# 02_-_WIRELESS_CHARGE.net
KiCad netlist of a schematic drawn in Altium Designer
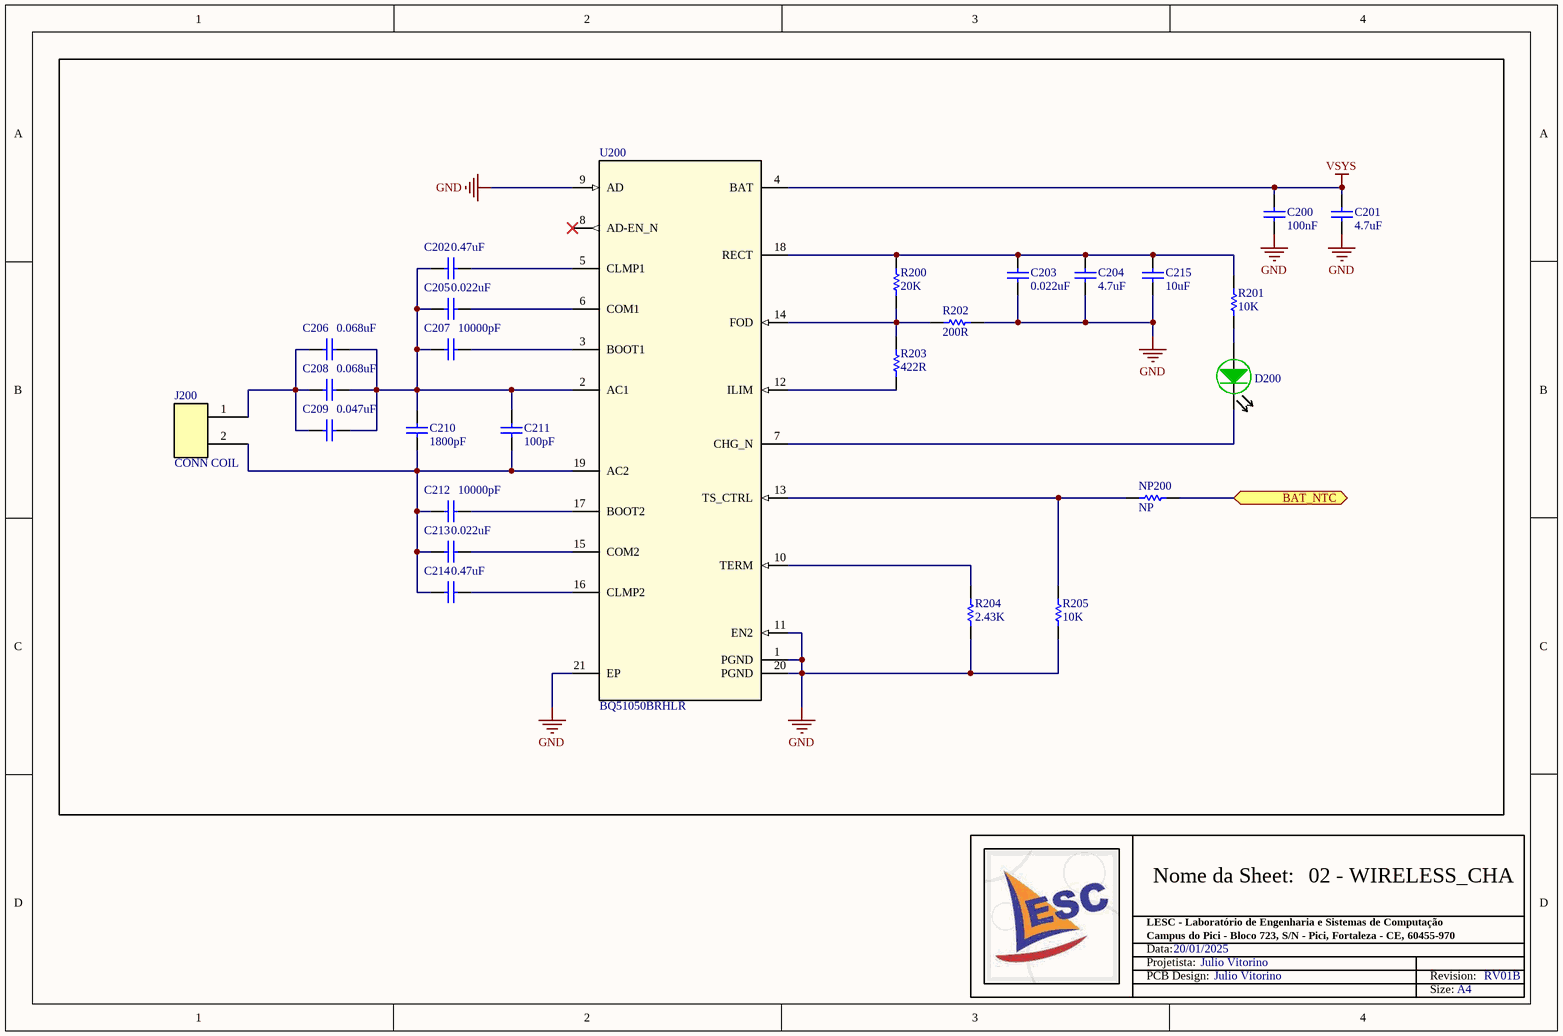
[diagram p0: 02 - WIRELESS_CHARGE.SchDoc]

(export (version "E")
  (design (tool "Eeschema 10.0.6"))
  (components
    (comp (ref "C200")
      (value "100nF")
      (footprint "0402-C-R")
      (description "CAP SMD 0402 MLCC GERAL 100nF 10V ±20% 0402 X7R PN:C0402C104K8RACTU KEMET")
      (fields (field (name "VOLTAGE") "10V") (field (name "TOLERANCE") "20%"))
      (libsource (lib "Schlib1") (part "CAP SMD 0402 100nF 10V ±20%"))
    )
    (comp (ref "C201")
      (value "4.7uF")
      (footprint "0402-C-R")
      (description "CAP SMD 0402 MLCC GERAL 4.7uF 10V ±20% 0402 X5R PN:GRM155R61A475MEAAD MURATA")
      (fields (field (name "VOLTAGE") "10V") (field (name "TOLERANCE") "20%"))
      (libsource (lib "Schlib1") (part "CAP SMD 0402 4.7uF 10V ±20%"))
    )
    (comp (ref "C202")
      (value "0.47uF")
      (footprint "0402-C-R")
      (description "CAP CER  0.47uF 50V X7R 0402 PN: GRM155R61H474KE11D")
      (fields (field (name "POWER") "50V") (field (name "TOLERANCE") "10%"))
      (libsource (lib "Schlib1") (part "CAP SMD 0402 0.47uF 50V ±10%"))
    )
    (comp (ref "C203")
      (value "0.022uF")
      (footprint "0402-C-R")
      (description "CAP CER  0.022uF 50V X7R 0402 PN: GCM155R71H223KA55D")
      (fields (field (name "POWER") "50V") (field (name "TOLERANCE") "10%"))
      (libsource (lib "Schlib1") (part "CAP SMD 0402 0.022uF 50V ±10%"))
    )
    (comp (ref "C204")
      (value "4.7uF")
      (footprint "0402-C-R")
      (description "CAP SMD 0402 MLCC GERAL 4.7uF 10V ±20% 0402 X5R PN:GRM155R61A475MEAAD MURATA")
      (fields (field (name "VOLTAGE") "10V") (field (name "TOLERANCE") "20%"))
      (libsource (lib "Schlib1") (part "CAP SMD 0402 4.7uF 10V ±20%"))
    )
    (comp (ref "C205")
      (value "0.022uF")
      (footprint "0402-C-R")
      (description "CAP CER  0.022uF 50V X7R 0402 PN: GCM155R71H223KA55D")
      (fields (field (name "POWER") "50V") (field (name "TOLERANCE") "10%"))
      (libsource (lib "Schlib1") (part "CAP SMD 0402 0.022uF 50V ±10%"))
    )
    (comp (ref "C206")
      (value "0.068uF")
      (footprint "0402-C-R")
      (description "CAP CER 0.068uF 50V X7R 0402 PN: GCM155R71H683KE02D")
      (fields (field (name "POWER") "50V") (field (name "TOLERANCE") "10%"))
      (libsource (lib "Schlib1") (part "CAP SMD 0402 0.068uF 50V ±10%"))
    )
    (comp (ref "C207")
      (value "10000pF")
      (footprint "0402-C-R")
      (description "CAP CER 10000PF 50V X7R 0402 PN: GCM155R71H103KA55D")
      (fields (field (name "POWER") "50V") (field (name "TOLERANCE") "10%"))
      (libsource (lib "Schlib1") (part "CAP SMD 0402 10000pF 50V ±10%"))
    )
    (comp (ref "C208")
      (value "0.068uF")
      (footprint "0402-C-R")
      (description "CAP CER 0.068uF 50V X7R 0402 PN: GCM155R71H683KE02D")
      (fields (field (name "POWER") "50V") (field (name "TOLERANCE") "10%"))
      (libsource (lib "Schlib1") (part "CAP SMD 0402 0.068uF 50V ±10%"))
    )
    (comp (ref "C209")
      (value "0.047uF")
      (footprint "0402-C-R")
      (description "CAP CER  0.047uF 50V X7R 0402 PN: GCM155R71H473KE02D")
      (fields (field (name "POWER") "50V") (field (name "TOLERANCE") "10%"))
      (libsource (lib "Schlib1") (part "CAP SMD 0402 0.047uF 50V ±10%"))
    )
    (comp (ref "C210")
      (value "1800pF")
      (footprint "0402-C-R")
      (description "CAP CER 1800PF 50V C0G/NP0 0402 PN: GRM1555C1H182JA01D")
      (fields (field (name "POWER") "50V") (field (name "TOLERANCE") "5%"))
      (libsource (lib "Schlib1") (part "CAP SMD 0402 1800pF 50V ±5%"))
    )
    (comp (ref "C211")
      (value "100pF")
      (footprint "0402-C-R")
      (description "CAP SMD CER 100pF 50V ±5% 0402 C0G,NP0 TAPE PN: GRM1555C1H101JA01D")
      (fields (field (name "POWER") "50V") (field (name "TOLERANCE") "1%"))
      (libsource (lib "Schlib1") (part "CAP SMD 0402 100pF 50V ±5%"))
    )
    (comp (ref "C212")
      (value "10000pF")
      (footprint "0402-C-R")
      (description "CAP CER 10000PF 50V X7R 0402 PN: GCM155R71H103KA55D")
      (fields (field (name "POWER") "50V") (field (name "TOLERANCE") "10%"))
      (libsource (lib "Schlib1") (part "CAP SMD 0402 10000pF 50V ±10%"))
    )
    (comp (ref "C213")
      (value "0.022uF")
      (footprint "0402-C-R")
      (description "CAP CER  0.022uF 50V X7R 0402 PN: GCM155R71H223KA55D")
      (fields (field (name "POWER") "50V") (field (name "TOLERANCE") "10%"))
      (libsource (lib "Schlib1") (part "CAP SMD 0402 0.022uF 50V ±10%"))
    )
    (comp (ref "C214")
      (value "0.47uF")
      (footprint "0402-C-R")
      (description "CAP CER  0.47uF 50V X7R 0402 PN: GRM155R61H474KE11D")
      (fields (field (name "POWER") "50V") (field (name "TOLERANCE") "10%"))
      (libsource (lib "Schlib1") (part "CAP SMD 0402 0.47uF 50V ±10%"))
    )
    (comp (ref "C215")
      (value "10uF")
      (footprint "0603-C-R")
      (description "CAP SMD 0603 MLCC GERAL 10uF 10V ±10% X7R PN: GRM188Z71A106KA73D")
      (fields (field (name "VOLTAGE") "10V") (field (name "TOLERANCE") "10%"))
      (libsource (lib "Schlib1") (part "CAP SMD 0603 10uF 10V ±10%"))
    )
    (comp (ref "D200")
      (value "150060GS75000")
      (footprint "LED0603")
      (description "LED SMD VD ALTO BRILHO 1,6x0,8x0,8mm 430mcd PN:150060GS75000 0603 WURTH")
      (libsource (lib "Schlib1") (part "LED SMD VD 0603"))
    )
    (comp (ref "J200")
      (value "CONN COIL")
      (footprint "CONNECTOR COIL")
      (description "COIL CONNECTOR")
      (libsource (lib "Schlib1") (part "CONN COIL"))
    )
    (comp (ref "NP200")
      (value "NP")
      (footprint "0402-R-NP")
      (description "RES SMD 0402 NP")
      (libsource (lib "Schlib1") (part "RES SMD 0402 NP"))
    )
    (comp (ref "R200")
      (value "20K")
      (footprint "0402-R-R")
      (description "RES SMD GERAL FILM 20K 0.063W ±1% 0402 7\" TAPE PN: RMCF0402FT20K0 STACKPOLE")
      (fields (field (name "POWER") "0.063W") (field (name "TOLERANCE") "1%"))
      (libsource (lib "Schlib1") (part "RES SMD 0402 20K 0.063W ±1%"))
    )
    (comp (ref "R201")
      (value "10K")
      (footprint "0402-R-R")
      (description "RES SMD GERAL FILM 10K 0.063W ±1% 0402 7\" TAPE PN: RMCF0402FT10K0 STACKPOLE")
      (fields (field (name "POWER") "0.063W") (field (name "TOLERANCE") "1%"))
      (libsource (lib "Schlib1") (part "RES SMD 0402 10K 0.063W ±1%"))
    )
    (comp (ref "R202")
      (value "200R")
      (footprint "0402-R-R")
      (description "RES SMD GERAL FILM 200R 0.063W ±1% 0402 7\" TAPE PN: RMCF0402JT200R STACKPOLE")
      (fields (field (name "POWER") "0.063W") (field (name "TOLERANCE") "1%"))
      (libsource (lib "Schlib1") (part "RES SMD 0402 200R 0.063W ±1%"))
    )
    (comp (ref "R203")
      (value "422R")
      (footprint "0402-R-R")
      (description "RES SMD GERAL FILM 422R 0.063W ±1% 0402 7\" TAPE PN: RMCF0402FT422R STACKPOLE")
      (fields (field (name "POWER") "0.063W") (field (name "TOLERANCE") "1%"))
      (libsource (lib "Schlib1") (part "RES SMD 0402 422R 0.063W ±1%"))
    )
    (comp (ref "R204")
      (value "2.43K")
      (footprint "0402-R-R")
      (description "RES SMD GERAL FILM 2.43K 0.063W ±1% 0402 7\" TAPE PN: RMCF0402FT2K43 STACKPOLE")
      (fields (field (name "POWER") "0.063W") (field (name "TOLERANCE") "1%"))
      (libsource (lib "Schlib1") (part "RES SMD 0402 2.43K 0.063W ±1%"))
    )
    (comp (ref "R205")
      (value "10K")
      (footprint "0402-R-R")
      (description "RES SMD GERAL FILM 10K 0.063W ±1% 0402 7\" TAPE PN: RMCF0402FT10K0 STACKPOLE")
      (fields (field (name "POWER") "0.063W") (field (name "TOLERANCE") "1%"))
      (libsource (lib "Schlib1") (part "RES SMD 0402 10K 0.063W ±1%"))
    )
    (comp (ref "U200")
      (value "BQ51050BRHLR")
      (footprint "RHL0020A")
      (description "Wireless Power Receiver PMIC 20-VQFN (3.5x4.5) PN: BQ51050BRHLR")
      (fields (field (name "PN") "BQ51050BRHLR"))
      (libsource (lib "Schlib1") (part "IC WIRELESS PWR RCVR 20QFN"))
    )
  )
  (nets
    (net (code "1") (name "/BAT_NTC") (class "Default")
      (node (ref "NP200") (pin "2") (pinfunction "2_2") (pintype "passive"))
    )
    (net (code "2") (name "GND") (class "Default")
      (node (ref "C200") (pin "1") (pinfunction "1_1") (pintype "passive"))
      (node (ref "C201") (pin "1") (pinfunction "1_1") (pintype "passive"))
      (node (ref "C203") (pin "1") (pinfunction "1_1") (pintype "passive"))
      (node (ref "C204") (pin "1") (pinfunction "1_1") (pintype "passive"))
      (node (ref "C215") (pin "1") (pinfunction "1_1") (pintype "passive"))
      (node (ref "R202") (pin "1") (pinfunction "1_1") (pintype "passive"))
      (node (ref "R204") (pin "1") (pinfunction "1_1") (pintype "passive"))
      (node (ref "R205") (pin "1") (pinfunction "1_1") (pintype "passive"))
      (node (ref "U200") (pin "1") (pinfunction "PGND_1") (pintype "power_in"))
      (node (ref "U200") (pin "11") (pinfunction "EN2_11") (pintype "input"))
      (node (ref "U200") (pin "20") (pinfunction "PGND_20") (pintype "power_in"))
      (node (ref "U200") (pin "21") (pinfunction "EP_21") (pintype "passive"))
      (node (ref "U200") (pin "9") (pinfunction "AD_9") (pintype "input"))
    )
    (net (code "3") (name "Net-(C206-Pad1)") (class "Default")
      (node (ref "C206") (pin "1") (pinfunction "1_1") (pintype "passive"))
      (node (ref "C208") (pin "1") (pinfunction "1_1") (pintype "passive"))
      (node (ref "C209") (pin "1") (pinfunction "1_1") (pintype "passive"))
      (node (ref "J200") (pin "1") (pintype "passive"))
    )
    (net (code "4") (name "Net-(D200-A)") (class "Default")
      (node (ref "D200") (pin "2") (pinfunction "A_2") (pintype "passive"))
      (node (ref "R201") (pin "1") (pinfunction "1_1") (pintype "passive"))
    )
    (net (code "5") (name "Net-(D200-K)") (class "Default")
      (node (ref "D200") (pin "1") (pinfunction "K_1") (pintype "passive"))
      (node (ref "U200") (pin "7") (pinfunction "CHG_N_7") (pintype "open_collector"))
    )
    (net (code "6") (name "Net-(U200-AC1)") (class "Default")
      (node (ref "C202") (pin "1") (pinfunction "1_1") (pintype "passive"))
      (node (ref "C205") (pin "1") (pinfunction "1_1") (pintype "passive"))
      (node (ref "C206") (pin "2") (pinfunction "2_2") (pintype "passive"))
      (node (ref "C207") (pin "1") (pinfunction "1_1") (pintype "passive"))
      (node (ref "C208") (pin "2") (pinfunction "2_2") (pintype "passive"))
      (node (ref "C209") (pin "2") (pinfunction "2_2") (pintype "passive"))
      (node (ref "C210") (pin "2") (pinfunction "2_2") (pintype "passive"))
      (node (ref "C211") (pin "2") (pinfunction "2_2") (pintype "passive"))
      (node (ref "U200") (pin "2") (pinfunction "AC1_2") (pintype "power_in"))
    )
    (net (code "7") (name "Net-(U200-AC2)") (class "Default")
      (node (ref "C210") (pin "1") (pinfunction "1_1") (pintype "passive"))
      (node (ref "C211") (pin "1") (pinfunction "1_1") (pintype "passive"))
      (node (ref "C212") (pin "1") (pinfunction "1_1") (pintype "passive"))
      (node (ref "C213") (pin "1") (pinfunction "1_1") (pintype "passive"))
      (node (ref "C214") (pin "1") (pinfunction "1_1") (pintype "passive"))
      (node (ref "J200") (pin "2") (pintype "passive"))
      (node (ref "U200") (pin "19") (pinfunction "AC2_19") (pintype "power_in"))
    )
    (net (code "8") (name "Net-(U200-BOOT1)") (class "Default")
      (node (ref "C207") (pin "2") (pinfunction "2_2") (pintype "passive"))
      (node (ref "U200") (pin "3") (pinfunction "BOOT1_3") (pintype "passive"))
    )
    (net (code "9") (name "Net-(U200-BOOT2)") (class "Default")
      (node (ref "C212") (pin "2") (pinfunction "2_2") (pintype "passive"))
      (node (ref "U200") (pin "17") (pinfunction "BOOT2_17") (pintype "passive"))
    )
    (net (code "10") (name "Net-(U200-CLMP1)") (class "Default")
      (node (ref "C202") (pin "2") (pinfunction "2_2") (pintype "passive"))
      (node (ref "U200") (pin "5") (pinfunction "CLMP1_5") (pintype "open_collector"))
    )
    (net (code "11") (name "Net-(U200-CLMP2)") (class "Default")
      (node (ref "C214") (pin "2") (pinfunction "2_2") (pintype "passive"))
      (node (ref "U200") (pin "16") (pinfunction "CLMP2_16") (pintype "open_collector"))
    )
    (net (code "12") (name "Net-(U200-COM1)") (class "Default")
      (node (ref "C205") (pin "2") (pinfunction "2_2") (pintype "passive"))
      (node (ref "U200") (pin "6") (pinfunction "COM1_6") (pintype "open_collector"))
    )
    (net (code "13") (name "Net-(U200-COM2)") (class "Default")
      (node (ref "C213") (pin "2") (pinfunction "2_2") (pintype "passive"))
      (node (ref "U200") (pin "15") (pinfunction "COM2_15") (pintype "open_collector"))
    )
    (net (code "14") (name "Net-(U200-FOD)") (class "Default")
      (node (ref "R200") (pin "2") (pinfunction "2_2") (pintype "passive"))
      (node (ref "R202") (pin "2") (pinfunction "2_2") (pintype "passive"))
      (node (ref "R203") (pin "2") (pinfunction "2_2") (pintype "passive"))
      (node (ref "U200") (pin "14") (pinfunction "FOD_14") (pintype "input"))
    )
    (net (code "15") (name "Net-(U200-ILIM)") (class "Default")
      (node (ref "R203") (pin "1") (pinfunction "1_1") (pintype "passive"))
      (node (ref "U200") (pin "12") (pinfunction "ILIM_12") (pintype "input"))
    )
    (net (code "16") (name "Net-(U200-RECT)") (class "Default")
      (node (ref "C203") (pin "2") (pinfunction "2_2") (pintype "passive"))
      (node (ref "C204") (pin "2") (pinfunction "2_2") (pintype "passive"))
      (node (ref "C215") (pin "2") (pinfunction "2_2") (pintype "passive"))
      (node (ref "R200") (pin "1") (pinfunction "1_1") (pintype "passive"))
      (node (ref "R201") (pin "2") (pinfunction "2_2") (pintype "passive"))
      (node (ref "U200") (pin "18") (pinfunction "RECT_18") (pintype "passive"))
    )
    (net (code "17") (name "Net-(U200-TERM)") (class "Default")
      (node (ref "R204") (pin "2") (pinfunction "2_2") (pintype "passive"))
      (node (ref "U200") (pin "10") (pinfunction "TERM_10") (pintype "input"))
    )
    (net (code "18") (name "Net-(U200-TS_CTRL)") (class "Default")
      (node (ref "NP200") (pin "1") (pinfunction "1_1") (pintype "passive"))
      (node (ref "R205") (pin "2") (pinfunction "2_2") (pintype "passive"))
      (node (ref "U200") (pin "13") (pinfunction "TS_CTRL_13") (pintype "input"))
    )
    (net (code "19") (name "VSYS") (class "Default")
      (node (ref "C200") (pin "2") (pinfunction "2_2") (pintype "passive"))
      (node (ref "C201") (pin "2") (pinfunction "2_2") (pintype "passive"))
      (node (ref "U200") (pin "4") (pinfunction "BAT_4") (pintype "power_in"))
    )
    (net (code "20") (name "unconnected-(U200-AD-EN_N-Pad8)") (class "Default")
      (node (ref "U200") (pin "8") (pinfunction "AD-EN_N_8") (pintype "output+no_connect"))
    )
  )
)
